# voltage_sensor_v0_6.net
KiCad netlist of a schematic drawn in EAGLE
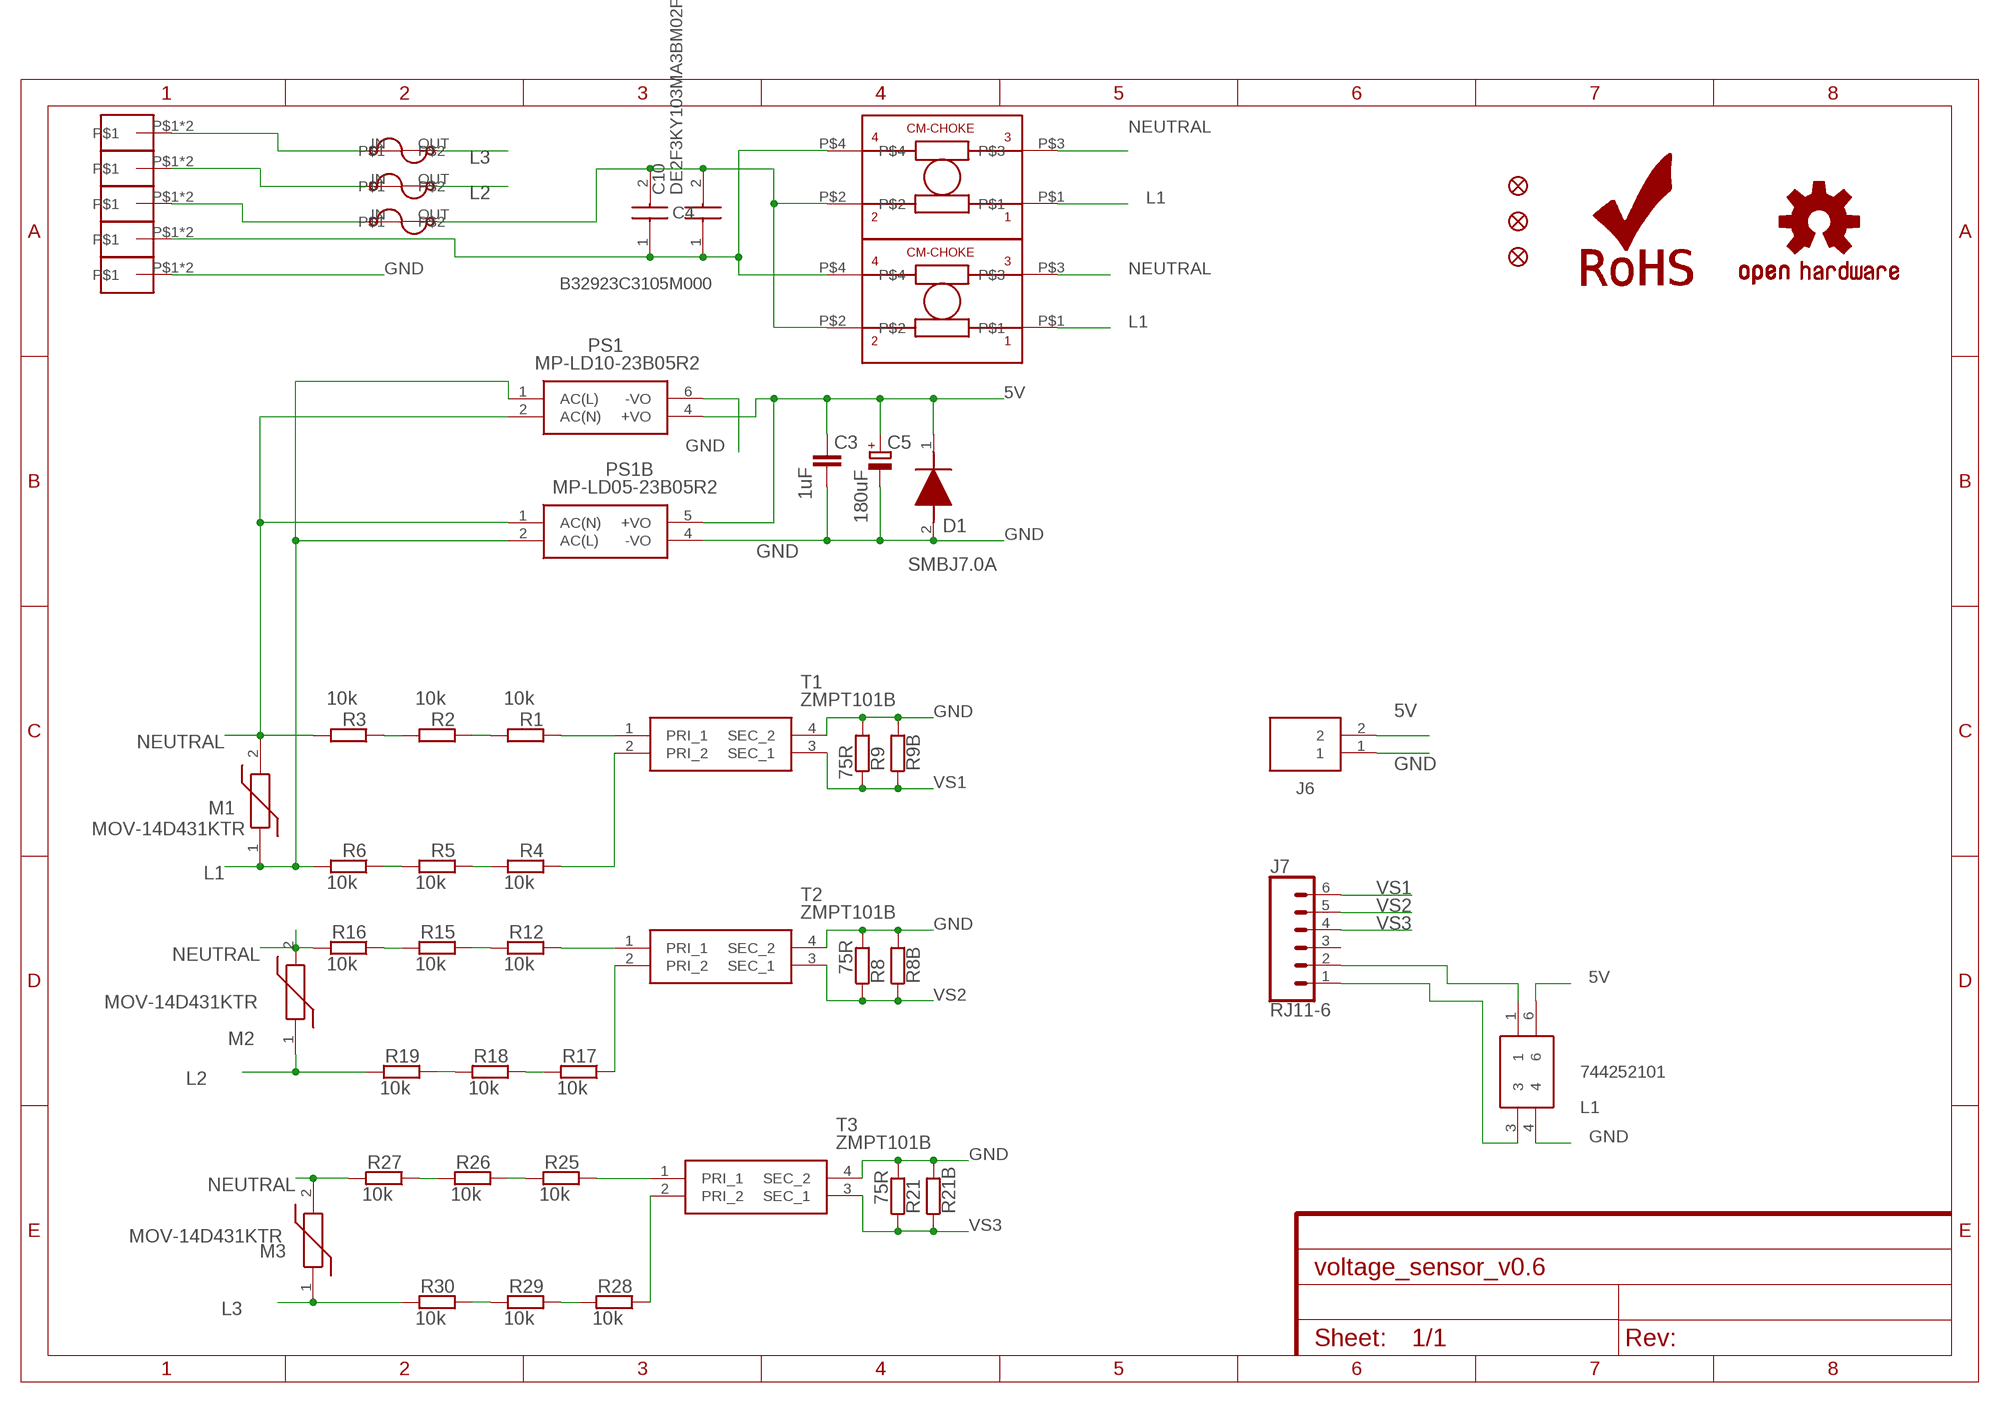
[diagram p0: schematic, sheet 1]

(export (version "E")
  (design (tool "Eeschema 10.0.6"))
  (components
    (comp (ref "C3")
      (value "1uF")
      (footprint "eagle-import:C0603")
      (libsource (lib "eagle-import") (part "C-EUC0603"))
    )
    (comp (ref "C4")
      (value "B32923C3105M000")
      (footprint "eagle-import:B32923C_(26.5_X_12)")
      (libsource (lib "eagle-import") (part "B32923C3105M000"))
    )
    (comp (ref "C5")
      (value "180uF")
      (footprint "eagle-import:PANASONIC_C")
      (libsource (lib "eagle-import") (part "CPOL-EUC"))
    )
    (comp (ref "C10")
      (value "DE2F3KY103MA3BM02F")
      (footprint "eagle-import:DE2F3KY103MA3BM02F")
      (fields (field (name "MOUSER_PART_NUMBER") "81-DE2F3KY103MA3BM2F"))
      (libsource (lib "eagle-import") (part "DE2F3KY103MA3BM02F"))
    )
    (comp (ref "D1")
      (value "SMBJ7.0A")
      (footprint "eagle-import:DIOM5336X244N")
      (libsource (lib "eagle-import") (part "SMBJ7.0A"))
    )
    (comp (ref "F1")
      (value "2A/250V")
      (footprint "eagle-import:BELFUSE1A")
      (libsource (lib "eagle-import") (part "BEL1AFUSE"))
    )
    (comp (ref "F2")
      (value "2A/250V")
      (footprint "eagle-import:BELFUSE1A")
      (libsource (lib "eagle-import") (part "BEL1AFUSE"))
    )
    (comp (ref "F3")
      (value "2A/250V")
      (footprint "eagle-import:BELFUSE1A")
      (libsource (lib "eagle-import") (part "BEL1AFUSE"))
    )
    (comp (ref "FD1")
      (value "FIDUCIAL1X2")
      (footprint "eagle-import:FIDUCIAL-1X2")
      (libsource (lib "eagle-import") (part "FIDUCIAL1X2"))
    )
    (comp (ref "FD2")
      (value "FIDUCIAL1X2")
      (footprint "eagle-import:FIDUCIAL-1X2")
      (libsource (lib "eagle-import") (part "FIDUCIAL1X2"))
    )
    (comp (ref "FD3")
      (value "FIDUCIAL1X2")
      (footprint "eagle-import:FIDUCIAL-1X2")
      (libsource (lib "eagle-import") (part "FIDUCIAL1X2"))
    )
    (comp (ref "J1")
      (value "1905010")
      (footprint "eagle-import:1905010")
      (libsource (lib "eagle-import") (part "1905010"))
    )
    (comp (ref "J3")
      (value "1905010")
      (footprint "eagle-import:1905010")
      (libsource (lib "eagle-import") (part "1905010"))
    )
    (comp (ref "J4")
      (value "1905010")
      (footprint "eagle-import:1905010")
      (libsource (lib "eagle-import") (part "1905010"))
    )
    (comp (ref "J5")
      (value "1905010")
      (footprint "eagle-import:1905010")
      (libsource (lib "eagle-import") (part "1905010"))
    )
    (comp (ref "J6")
      (value "20020316-H021B01LF")
      (footprint "eagle-import:20020316H021B01LF")
      (libsource (lib "eagle-import") (part "20020316-H021B01LF"))
    )
    (comp (ref "J7")
      (value "RJ11-6")
      (footprint "eagle-import:RJ11-6")
      (libsource (lib "eagle-import") (part "RJ11-6"))
    )
    (comp (ref "L1")
      (value "744252101")
      (footprint "eagle-import:744252101")
      (fields (field (name "MOUSER_PART_NUMBER") "710-744252101"))
      (libsource (lib "eagle-import") (part "744252101"))
    )
    (comp (ref "LOGO1")
      (value "ROHS_LOGO")
      (footprint "eagle-import:ROHS_LOGO_0.18_IN")
      (libsource (lib "eagle-import") (part "ROHS_LOGO"))
    )
    (comp (ref "LOGO2")
      (value "OSHW-LOGOS-COPPER")
      (footprint "eagle-import:OSHW-LOGO-S_COPPER")
      (libsource (lib "eagle-import") (part "OSHW-LOGOS-COPPER"))
    )
    (comp (ref "M1")
      (value "MOV-14D431KTR")
      (footprint "eagle-import:MOV14D431KTR")
      (fields (field (name "MOUSER_PART_NUMBER") "652-MOV-14D431KTR"))
      (libsource (lib "eagle-import") (part "MOV-14D431KTR"))
    )
    (comp (ref "M2")
      (value "MOV-14D431KTR")
      (footprint "eagle-import:MOV14D431KTR")
      (fields (field (name "MOUSER_PART_NUMBER") "652-MOV-14D431KTR"))
      (libsource (lib "eagle-import") (part "MOV-14D431KTR"))
    )
    (comp (ref "M3")
      (value "MOV-14D431KTR")
      (footprint "eagle-import:MOV14D431KTR")
      (fields (field (name "MOUSER_PART_NUMBER") "652-MOV-14D431KTR"))
      (libsource (lib "eagle-import") (part "MOV-14D431KTR"))
    )
    (comp (ref "PS1")
      (value "MP-LD10-23B05R2")
      (footprint "eagle-import:MPLD1023B12R2")
      (libsource (lib "eagle-import") (part "MP-LD10-23B12R2"))
    )
    (comp (ref "PS1B")
      (value "MP-LD05-23B05R2")
      (footprint "eagle-import:MPLD0523B03R2")
      (fields (field (name "MANUFACTURER_PART_NUMBER") "MP-LD05-23B03R2"))
      (libsource (lib "eagle-import") (part "MP-LD05-23B03R2"))
    )
    (comp (ref "R1")
      (value "10k")
      (footprint "eagle-import:R0603")
      (libsource (lib "eagle-import") (part "R-EU_R0603"))
    )
    (comp (ref "R2")
      (value "10k")
      (footprint "eagle-import:R0603")
      (libsource (lib "eagle-import") (part "R-EU_R0603"))
    )
    (comp (ref "R3")
      (value "10k")
      (footprint "eagle-import:R0603")
      (libsource (lib "eagle-import") (part "R-EU_R0603"))
    )
    (comp (ref "R4")
      (value "10k")
      (footprint "eagle-import:R0603")
      (libsource (lib "eagle-import") (part "R-EU_R0603"))
    )
    (comp (ref "R5")
      (value "10k")
      (footprint "eagle-import:R0603")
      (libsource (lib "eagle-import") (part "R-EU_R0603"))
    )
    (comp (ref "R6")
      (value "10k")
      (footprint "eagle-import:R0603")
      (libsource (lib "eagle-import") (part "R-EU_R0603"))
    )
    (comp (ref "R8")
      (value "75R")
      (footprint "eagle-import:R0603")
      (libsource (lib "eagle-import") (part "R-EU_R0603"))
    )
    (comp (ref "R8B")
      (value "R-EU_0204/7")
      (footprint "eagle-import:0204_7")
      (libsource (lib "eagle-import") (part "R-EU_0204/7"))
    )
    (comp (ref "R9")
      (value "75R")
      (footprint "eagle-import:R0603")
      (libsource (lib "eagle-import") (part "R-EU_R0603"))
    )
    (comp (ref "R9B")
      (value "R-EU_0204/7")
      (footprint "eagle-import:0204_7")
      (libsource (lib "eagle-import") (part "R-EU_0204/7"))
    )
    (comp (ref "R12")
      (value "10k")
      (footprint "eagle-import:R0603")
      (libsource (lib "eagle-import") (part "R-EU_R0603"))
    )
    (comp (ref "R15")
      (value "10k")
      (footprint "eagle-import:R0603")
      (libsource (lib "eagle-import") (part "R-EU_R0603"))
    )
    (comp (ref "R16")
      (value "10k")
      (footprint "eagle-import:R0603")
      (libsource (lib "eagle-import") (part "R-EU_R0603"))
    )
    (comp (ref "R17")
      (value "10k")
      (footprint "eagle-import:R0603")
      (libsource (lib "eagle-import") (part "R-EU_R0603"))
    )
    (comp (ref "R18")
      (value "10k")
      (footprint "eagle-import:R0603")
      (libsource (lib "eagle-import") (part "R-EU_R0603"))
    )
    (comp (ref "R19")
      (value "10k")
      (footprint "eagle-import:R0603")
      (libsource (lib "eagle-import") (part "R-EU_R0603"))
    )
    (comp (ref "R21")
      (value "75R")
      (footprint "eagle-import:R0603")
      (libsource (lib "eagle-import") (part "R-EU_R0603"))
    )
    (comp (ref "R21B")
      (value "R-EU_0204/7")
      (footprint "eagle-import:0204_7")
      (libsource (lib "eagle-import") (part "R-EU_0204/7"))
    )
    (comp (ref "R25")
      (value "10k")
      (footprint "eagle-import:R0603")
      (libsource (lib "eagle-import") (part "R-EU_R0603"))
    )
    (comp (ref "R26")
      (value "10k")
      (footprint "eagle-import:R0603")
      (libsource (lib "eagle-import") (part "R-EU_R0603"))
    )
    (comp (ref "R27")
      (value "10k")
      (footprint "eagle-import:R0603")
      (libsource (lib "eagle-import") (part "R-EU_R0603"))
    )
    (comp (ref "R28")
      (value "10k")
      (footprint "eagle-import:R0603")
      (libsource (lib "eagle-import") (part "R-EU_R0603"))
    )
    (comp (ref "R29")
      (value "10k")
      (footprint "eagle-import:R0603")
      (libsource (lib "eagle-import") (part "R-EU_R0603"))
    )
    (comp (ref "R30")
      (value "10k")
      (footprint "eagle-import:R0603")
      (libsource (lib "eagle-import") (part "R-EU_R0603"))
    )
    (comp (ref "T1")
      (value "ZMPT101B")
      (footprint "eagle-import:ZMPT101B")
      (libsource (lib "eagle-import") (part "ZMPT101B"))
    )
    (comp (ref "T2")
      (value "ZMPT101B")
      (footprint "eagle-import:ZMPT101B")
      (libsource (lib "eagle-import") (part "ZMPT101B"))
    )
    (comp (ref "T3")
      (value "ZMPT101B")
      (footprint "eagle-import:ZMPT101B")
      (libsource (lib "eagle-import") (part "ZMPT101B"))
    )
    (comp (ref "U$1")
      (value "47mH")
      (footprint "eagle-import:RN114-0.3-02-47M")
      (libsource (lib "eagle-import") (part "RN114-0.3-02-47M"))
    )
    (comp (ref "U$1B")
      (value "RN214-0.3-02-47M")
      (footprint "eagle-import:RN214-0.3-02-47M")
      (libsource (lib "eagle-import") (part "RN214-0.3-02-47M"))
    )
    (comp (ref "U$6")
      (value "1905010")
      (footprint "eagle-import:1905010")
      (libsource (lib "eagle-import") (part "1905010"))
    )
  )
  (nets
    (net (code "1") (name "/5V") (class "Default")
      (node (ref "C3") (pin "1") (pinfunction "1_1") (pintype "passive"))
      (node (ref "C5") (pin "+") (pinfunction "+_+") (pintype "passive"))
      (node (ref "D1") (pin "1") (pinfunction "K_1") (pintype "bidirectional"))
      (node (ref "J6") (pin "2") (pinfunction "2_2") (pintype "bidirectional"))
      (node (ref "L1") (pin "6") (pinfunction "6_6") (pintype "bidirectional"))
      (node (ref "PS1") (pin "4") (pinfunction "+VO_4") (pintype "bidirectional"))
      (node (ref "PS1B") (pin "5") (pinfunction "+VO_5") (pintype "bidirectional"))
    )
    (net (code "2") (name "/GND") (class "Default")
      (node (ref "C3") (pin "2") (pinfunction "2_2") (pintype "passive"))
      (node (ref "C5") (pin "-") (pinfunction "-_-") (pintype "passive"))
      (node (ref "D1") (pin "2") (pinfunction "A_2") (pintype "bidirectional"))
      (node (ref "J1") (pin "P$1") (pinfunction "P$1_P$1") (pintype "bidirectional"))
      (node (ref "J1") (pin "P$2") (pinfunction "P$1_P$2") (pintype "bidirectional"))
      (node (ref "J6") (pin "1") (pinfunction "1_1") (pintype "bidirectional"))
      (node (ref "L1") (pin "4") (pinfunction "4_4") (pintype "bidirectional"))
      (node (ref "PS1") (pin "6") (pinfunction "-VO_6") (pintype "bidirectional"))
      (node (ref "PS1B") (pin "4") (pinfunction "-VO_4") (pintype "bidirectional"))
      (node (ref "R21") (pin "2") (pinfunction "2_2") (pintype "passive"))
      (node (ref "R21B") (pin "2") (pinfunction "2_2") (pintype "passive"))
      (node (ref "R8") (pin "2") (pinfunction "2_2") (pintype "passive"))
      (node (ref "R8B") (pin "2") (pinfunction "2_2") (pintype "passive"))
      (node (ref "R9") (pin "2") (pinfunction "2_2") (pintype "passive"))
      (node (ref "R9B") (pin "2") (pinfunction "2_2") (pintype "passive"))
      (node (ref "T1") (pin "4") (pinfunction "SEC_2_4") (pintype "bidirectional"))
      (node (ref "T2") (pin "4") (pinfunction "SEC_2_4") (pintype "bidirectional"))
      (node (ref "T3") (pin "4") (pinfunction "SEC_2_4") (pintype "bidirectional"))
    )
    (net (code "3") (name "/L1") (class "Default")
      (node (ref "M1") (pin "1") (pinfunction "1_1") (pintype "bidirectional"))
      (node (ref "PS1") (pin "1") (pinfunction "AC(L)_1") (pintype "bidirectional"))
      (node (ref "PS1B") (pin "2") (pinfunction "AC(L)_2") (pintype "bidirectional"))
      (node (ref "R6") (pin "2") (pinfunction "2_2") (pintype "passive"))
      (node (ref "U$1") (pin "P$1") (pinfunction "P$1_P$1") (pintype "bidirectional"))
      (node (ref "U$1B") (pin "P$1") (pinfunction "P$1_P$1") (pintype "bidirectional"))
    )
    (net (code "4") (name "/L2") (class "Default")
      (node (ref "F2") (pin "OUT") (pinfunction "P$1_OUT") (pintype "bidirectional"))
      (node (ref "M2") (pin "1") (pinfunction "1_1") (pintype "bidirectional"))
      (node (ref "R19") (pin "2") (pinfunction "2_2") (pintype "passive"))
    )
    (net (code "5") (name "/L3") (class "Default")
      (node (ref "F3") (pin "OUT") (pinfunction "P$1_OUT") (pintype "bidirectional"))
      (node (ref "M3") (pin "1") (pinfunction "1_1") (pintype "bidirectional"))
      (node (ref "R30") (pin "2") (pinfunction "2_2") (pintype "passive"))
    )
    (net (code "6") (name "/NEUTRAL") (class "Default")
      (node (ref "M1") (pin "2") (pinfunction "2_2") (pintype "bidirectional"))
      (node (ref "M2") (pin "2") (pinfunction "2_2") (pintype "bidirectional"))
      (node (ref "M3") (pin "2") (pinfunction "2_2") (pintype "bidirectional"))
      (node (ref "PS1") (pin "2") (pinfunction "AC(N)_2") (pintype "bidirectional"))
      (node (ref "PS1B") (pin "1") (pinfunction "AC(N)_1") (pintype "bidirectional"))
      (node (ref "R16") (pin "2") (pinfunction "2_2") (pintype "passive"))
      (node (ref "R27") (pin "2") (pinfunction "2_2") (pintype "passive"))
      (node (ref "R3") (pin "2") (pinfunction "2_2") (pintype "passive"))
      (node (ref "U$1") (pin "P$3") (pinfunction "P$3_P$3") (pintype "bidirectional"))
      (node (ref "U$1B") (pin "P$3") (pinfunction "P$3_P$3") (pintype "bidirectional"))
    )
    (net (code "7") (name "/VS1") (class "Default")
      (node (ref "J7") (pin "6") (pinfunction "6_6") (pintype "passive"))
      (node (ref "R9") (pin "1") (pinfunction "1_1") (pintype "passive"))
      (node (ref "R9B") (pin "1") (pinfunction "1_1") (pintype "passive"))
      (node (ref "T1") (pin "3") (pinfunction "SEC_1_3") (pintype "bidirectional"))
    )
    (net (code "8") (name "/VS2") (class "Default")
      (node (ref "J7") (pin "5") (pinfunction "5_5") (pintype "passive"))
      (node (ref "R8") (pin "1") (pinfunction "1_1") (pintype "passive"))
      (node (ref "R8B") (pin "1") (pinfunction "1_1") (pintype "passive"))
      (node (ref "T2") (pin "3") (pinfunction "SEC_1_3") (pintype "bidirectional"))
    )
    (net (code "9") (name "/VS3") (class "Default")
      (node (ref "J7") (pin "4") (pinfunction "4_4") (pintype "passive"))
      (node (ref "R21") (pin "1") (pinfunction "1_1") (pintype "passive"))
      (node (ref "R21B") (pin "1") (pinfunction "1_1") (pintype "passive"))
      (node (ref "T3") (pin "3") (pinfunction "SEC_1_3") (pintype "bidirectional"))
    )
    (net (code "10") (name "Net-(C10-Pad1)") (class "Default")
      (node (ref "C10") (pin "1") (pinfunction "1_1") (pintype "bidirectional"))
      (node (ref "C4") (pin "1") (pinfunction "1_1") (pintype "bidirectional"))
      (node (ref "U$1") (pin "P$4") (pinfunction "P$4_P$4") (pintype "bidirectional"))
      (node (ref "U$1B") (pin "P$4") (pinfunction "P$4_P$4") (pintype "bidirectional"))
      (node (ref "U$6") (pin "P$1") (pinfunction "P$1_P$1") (pintype "bidirectional"))
      (node (ref "U$6") (pin "P$2") (pinfunction "P$1_P$2") (pintype "bidirectional"))
    )
    (net (code "11") (name "Net-(F1-P$1)") (class "Default")
      (node (ref "C10") (pin "2") (pinfunction "2_2") (pintype "bidirectional"))
      (node (ref "C4") (pin "2") (pinfunction "2_2") (pintype "bidirectional"))
      (node (ref "F1") (pin "OUT") (pinfunction "P$1_OUT") (pintype "bidirectional"))
      (node (ref "U$1") (pin "P$2") (pinfunction "P$2_P$2") (pintype "bidirectional"))
      (node (ref "U$1B") (pin "P$2") (pinfunction "P$2_P$2") (pintype "bidirectional"))
    )
    (net (code "12") (name "Net-(F1-P$2)") (class "Default")
      (node (ref "F1") (pin "IN") (pinfunction "P$2_IN") (pintype "bidirectional"))
      (node (ref "J3") (pin "P$1") (pinfunction "P$1_P$1") (pintype "bidirectional"))
      (node (ref "J3") (pin "P$2") (pinfunction "P$1_P$2") (pintype "bidirectional"))
    )
    (net (code "13") (name "Net-(F2-P$2)") (class "Default")
      (node (ref "F2") (pin "IN") (pinfunction "P$2_IN") (pintype "bidirectional"))
      (node (ref "J4") (pin "P$1") (pinfunction "P$1_P$1") (pintype "bidirectional"))
      (node (ref "J4") (pin "P$2") (pinfunction "P$1_P$2") (pintype "bidirectional"))
    )
    (net (code "14") (name "Net-(F3-P$2)") (class "Default")
      (node (ref "F3") (pin "IN") (pinfunction "P$2_IN") (pintype "bidirectional"))
      (node (ref "J5") (pin "P$1") (pinfunction "P$1_P$1") (pintype "bidirectional"))
      (node (ref "J5") (pin "P$2") (pinfunction "P$1_P$2") (pintype "bidirectional"))
    )
    (net (code "15") (name "Net-(J7-Pad1)") (class "Default")
      (node (ref "J7") (pin "1") (pinfunction "1_1") (pintype "passive"))
      (node (ref "L1") (pin "3") (pinfunction "3_3") (pintype "bidirectional"))
    )
    (net (code "16") (name "Net-(J7-Pad2)") (class "Default")
      (node (ref "J7") (pin "2") (pinfunction "2_2") (pintype "passive"))
      (node (ref "L1") (pin "1") (pinfunction "1_1") (pintype "bidirectional"))
    )
    (net (code "17") (name "Net-(R1-Pad2)") (class "Default")
      (node (ref "R1") (pin "2") (pinfunction "2_2") (pintype "passive"))
      (node (ref "R2") (pin "1") (pinfunction "1_1") (pintype "passive"))
    )
    (net (code "18") (name "Net-(R2-Pad2)") (class "Default")
      (node (ref "R2") (pin "2") (pinfunction "2_2") (pintype "passive"))
      (node (ref "R3") (pin "1") (pinfunction "1_1") (pintype "passive"))
    )
    (net (code "19") (name "Net-(R4-Pad2)") (class "Default")
      (node (ref "R4") (pin "2") (pinfunction "2_2") (pintype "passive"))
      (node (ref "R5") (pin "1") (pinfunction "1_1") (pintype "passive"))
    )
    (net (code "20") (name "Net-(R5-Pad2)") (class "Default")
      (node (ref "R5") (pin "2") (pinfunction "2_2") (pintype "passive"))
      (node (ref "R6") (pin "1") (pinfunction "1_1") (pintype "passive"))
    )
    (net (code "21") (name "Net-(R12-Pad2)") (class "Default")
      (node (ref "R12") (pin "2") (pinfunction "2_2") (pintype "passive"))
      (node (ref "R15") (pin "1") (pinfunction "1_1") (pintype "passive"))
    )
    (net (code "22") (name "Net-(R15-Pad2)") (class "Default")
      (node (ref "R15") (pin "2") (pinfunction "2_2") (pintype "passive"))
      (node (ref "R16") (pin "1") (pinfunction "1_1") (pintype "passive"))
    )
    (net (code "23") (name "Net-(R17-Pad2)") (class "Default")
      (node (ref "R17") (pin "2") (pinfunction "2_2") (pintype "passive"))
      (node (ref "R18") (pin "1") (pinfunction "1_1") (pintype "passive"))
    )
    (net (code "24") (name "Net-(R18-Pad2)") (class "Default")
      (node (ref "R18") (pin "2") (pinfunction "2_2") (pintype "passive"))
      (node (ref "R19") (pin "1") (pinfunction "1_1") (pintype "passive"))
    )
    (net (code "25") (name "Net-(R25-Pad2)") (class "Default")
      (node (ref "R25") (pin "2") (pinfunction "2_2") (pintype "passive"))
      (node (ref "R26") (pin "1") (pinfunction "1_1") (pintype "passive"))
    )
    (net (code "26") (name "Net-(R26-Pad2)") (class "Default")
      (node (ref "R26") (pin "2") (pinfunction "2_2") (pintype "passive"))
      (node (ref "R27") (pin "1") (pinfunction "1_1") (pintype "passive"))
    )
    (net (code "27") (name "Net-(R28-Pad2)") (class "Default")
      (node (ref "R28") (pin "2") (pinfunction "2_2") (pintype "passive"))
      (node (ref "R29") (pin "1") (pinfunction "1_1") (pintype "passive"))
    )
    (net (code "28") (name "Net-(R29-Pad2)") (class "Default")
      (node (ref "R29") (pin "2") (pinfunction "2_2") (pintype "passive"))
      (node (ref "R30") (pin "1") (pinfunction "1_1") (pintype "passive"))
    )
    (net (code "29") (name "Net-(T1-PRI_1)") (class "Default")
      (node (ref "R1") (pin "1") (pinfunction "1_1") (pintype "passive"))
      (node (ref "T1") (pin "1") (pinfunction "PRI_1_1") (pintype "bidirectional"))
    )
    (net (code "30") (name "Net-(T1-PRI_2)") (class "Default")
      (node (ref "R4") (pin "1") (pinfunction "1_1") (pintype "passive"))
      (node (ref "T1") (pin "2") (pinfunction "PRI_2_2") (pintype "bidirectional"))
    )
    (net (code "31") (name "Net-(T2-PRI_1)") (class "Default")
      (node (ref "R12") (pin "1") (pinfunction "1_1") (pintype "passive"))
      (node (ref "T2") (pin "1") (pinfunction "PRI_1_1") (pintype "bidirectional"))
    )
    (net (code "32") (name "Net-(T2-PRI_2)") (class "Default")
      (node (ref "R17") (pin "1") (pinfunction "1_1") (pintype "passive"))
      (node (ref "T2") (pin "2") (pinfunction "PRI_2_2") (pintype "bidirectional"))
    )
    (net (code "33") (name "Net-(T3-PRI_1)") (class "Default")
      (node (ref "R25") (pin "1") (pinfunction "1_1") (pintype "passive"))
      (node (ref "T3") (pin "1") (pinfunction "PRI_1_1") (pintype "bidirectional"))
    )
    (net (code "34") (name "Net-(T3-PRI_2)") (class "Default")
      (node (ref "R28") (pin "1") (pinfunction "1_1") (pintype "passive"))
      (node (ref "T3") (pin "2") (pinfunction "PRI_2_2") (pintype "bidirectional"))
    )
    (net (code "35") (name "unconnected-(J7-Pad3)") (class "Default")
      (node (ref "J7") (pin "3") (pinfunction "3_3") (pintype "passive"))
    )
  )
)
